# design.net
KiCad netlist of a schematic drawn in Altium Designer
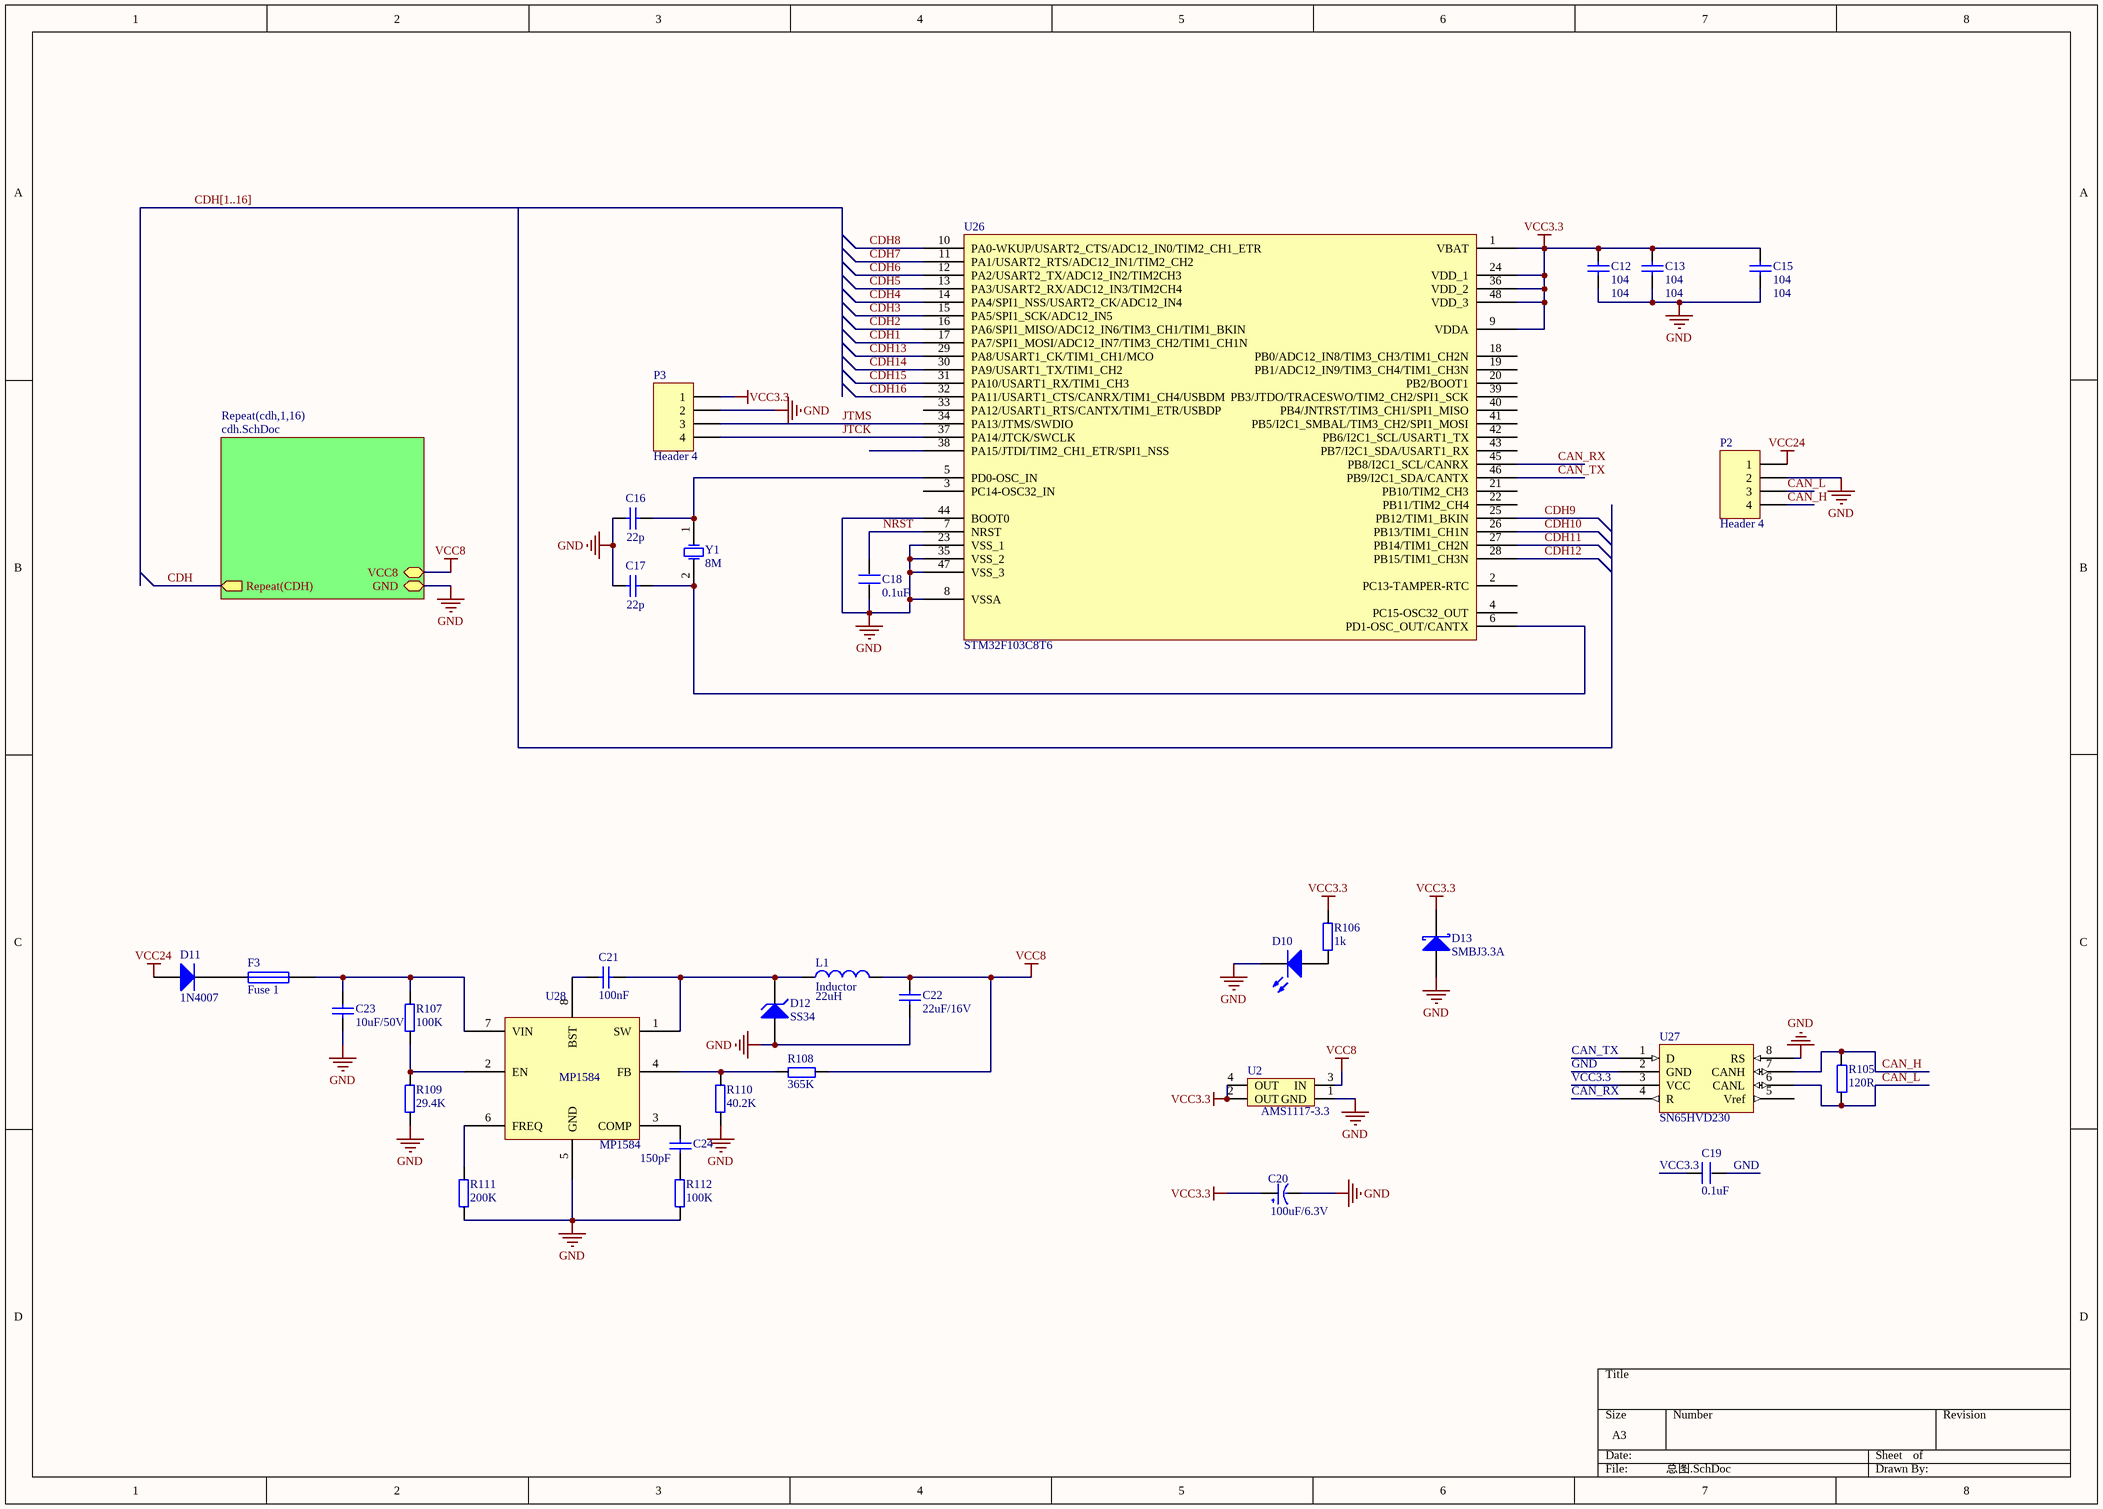
[diagram p0: 总图.SchDoc]

(export (version "E")
  (design (tool "Eeschema 10.0.6"))
  (components
    (comp (ref "C12")
      (value "104")
      (footprint "0603-CAP")
      (description "Capacitor")
      (fields (field (name "ALTIUM_VALUE") "104") (field (name "PUBLISHER") "Altium Limited"))
      (libsource (lib "Miscellaneous Devices") (part "Cap"))
    )
    (comp (ref "C13")
      (value "104")
      (footprint "0603-CAP")
      (description "Capacitor")
      (fields (field (name "ALTIUM_VALUE") "104") (field (name "PUBLISHER") "Altium Limited"))
      (libsource (lib "Miscellaneous Devices") (part "Cap"))
    )
    (comp (ref "C15")
      (value "104")
      (footprint "0603-CAP")
      (description "Capacitor")
      (fields (field (name "ALTIUM_VALUE") "104") (field (name "PUBLISHER") "Altium Limited"))
      (libsource (lib "Miscellaneous Devices") (part "Cap"))
    )
    (comp (ref "C16")
      (value "22p")
      (footprint "0603-CAP")
      (description "Capacitor")
      (fields (field (name "PUBLISHER") "Altium Limited"))
      (libsource (lib "Miscellaneous Devices") (part "Cap"))
    )
    (comp (ref "C17")
      (value "22p")
      (footprint "0603-CAP")
      (description "Capacitor")
      (fields (field (name "PUBLISHER") "Altium Limited"))
      (libsource (lib "Miscellaneous Devices") (part "Cap"))
    )
    (comp (ref "C18")
      (value "0.1uF")
      (footprint "0603-CAP")
      (libsource (lib "Explorer STM32F407封装库") (part "C"))
    )
    (comp (ref "C19")
      (value "0.1uF")
      (footprint "0603-CAP")
      (libsource (lib "Explorer STM32F407封装库") (part "C_3"))
    )
    (comp (ref "C20") (value "100uF/6.3V") (footprint "3216") (libsource (lib "WarShip V3_SCH") (part "CAP")))
    (comp (ref "C21")
      (value "100nF")
      (footprint "0603-CAP")
      (description "Capacitor (Semiconductor SIM Model)")
      (fields (field (name "Comment") "0.1uF") (field (name "PUBLISHER") "Altium Limited"))
      (libsource (lib "Miscellaneous Devices") (part "Cap Semi"))
    )
    (comp (ref "C22")
      (value "22uF/16V")
      (footprint "1206")
      (description "Capacitor (Semiconductor SIM Model)")
      (fields (field (name "PUBLISHER") "Altium Limited"))
      (libsource (lib "Miscellaneous Devices") (part "Cap Semi"))
    )
    (comp (ref "C23")
      (value "10uF/50V")
      (footprint "1206")
      (description "Capacitor (Semiconductor SIM Model)")
      (fields (field (name "PUBLISHER") "Altium Limited"))
      (libsource (lib "Miscellaneous Devices") (part "Cap Semi"))
    )
    (comp (ref "C24")
      (value "150pF")
      (footprint "0603-CAP")
      (description "Capacitor (Semiconductor SIM Model)")
      (fields (field (name "Comment") "0.1uF") (field (name "PUBLISHER") "Altium Limited"))
      (libsource (lib "Miscellaneous Devices") (part "Cap Semi"))
    )
    (comp (ref "D10")
      (value "LED0")
      (footprint "LC-0805_LED_S1")
      (description "Typical INFRARED GaAs LED")
      (fields (field (name "PUBLISHER") "Altium Limited"))
      (libsource (lib "继电器板_1") (part "LED0"))
    )
    (comp (ref "D11")
      (value "1N4007")
      (footprint "SMA(DO-214AC)_S1")
      (description "Default Diode")
      (fields (field (name "PUBLISHER") "Altium Limited"))
      (libsource (lib "Miscellaneous Devices") (part "Diode"))
    )
    (comp (ref "D12")
      (value "SS34")
      (footprint "SMA(DO-214AC)_S1")
      (description "Zener Diode")
      (fields (field (name "PUBLISHER") "Altium Limited"))
      (libsource (lib "Miscellaneous Devices") (part "D Zener"))
    )
    (comp (ref "D13")
      (value "SMBJ3.3A")
      (footprint "SMB(DO-214AA)_S1")
      (description "Schottky Rectifier")
      (fields (field (name "PUBLISHER") "Altium Limited"))
      (libsource (lib "Miscellaneous Devices") (part "Diode 18TQ045"))
    )
    (comp (ref "F3")
      (value "Fuse 1")
      (footprint "1206")
      (description "Fuse")
      (fields (field (name "PUBLISHER") "Altium Limited"))
      (libsource (lib "Miscellaneous Devices") (part "Fuse 1"))
    )
    (comp (ref "L1")
      (value "Inductor")
      (footprint "L-7*7*4mm-S")
      (fields (field (name "ALTIUM_VALUE") "22uH") (field (name "PUBLISHER") "Altium Limited"))
      (libsource (lib "Miscellaneous Devices") (part "Inductor"))
    )
    (comp (ref "P2")
      (value "Header 4")
      (footprint "DZ-4-3.5")
      (description "Header, 4-Pin")
      (fields (field (name "PUBLISHER") "Altium Limited"))
      (libsource (lib "Miscellaneous Connectors") (part "Header 4"))
    )
    (comp (ref "P3")
      (value "Header 4")
      (footprint "HDR1X4")
      (description "Header, 4-Pin")
      (fields (field (name "PUBLISHER") "Altium Limited"))
      (libsource (lib "Miscellaneous Connectors") (part "Header 4"))
    )
    (comp (ref "R105")
      (value "120R")
      (footprint "0603")
      (libsource (lib "Explorer STM32F407封装库") (part "R_2"))
    )
    (comp (ref "R106") (value "1k") (footprint "0603") (libsource (lib "Explorer STM32F407封装库") (part "R_2")))
    (comp (ref "R107")
      (value "100K")
      (footprint "0603")
      (libsource (lib "Explorer STM32F407封装库") (part "R_2"))
    )
    (comp (ref "R108")
      (value "365K")
      (footprint "0603")
      (libsource (lib "Explorer STM32F407封装库") (part "R_2"))
    )
    (comp (ref "R109")
      (value "29.4K")
      (footprint "0603")
      (libsource (lib "Explorer STM32F407封装库") (part "R_2"))
    )
    (comp (ref "R110")
      (value "40.2K")
      (footprint "0603")
      (libsource (lib "Explorer STM32F407封装库") (part "R_2"))
    )
    (comp (ref "R111")
      (value "200K")
      (footprint "0603")
      (libsource (lib "Explorer STM32F407封装库") (part "R_2"))
    )
    (comp (ref "R112")
      (value "100K")
      (footprint "0603")
      (libsource (lib "Explorer STM32F407封装库") (part "R_2"))
    )
    (comp (ref "U2")
      (value "AMS1117-3.3")
      (footprint "LC-SOT-223")
      (libsource (lib "WarShip V3_SCH") (part "AMS1117"))
    )
    (comp (ref "U26")
      (value "STM32F103C8T6")
      (footprint "LC-LQFP-48")
      (libsource (lib "Schlib1") (part "stm32f103v8t6"))
    )
    (comp (ref "U27")
      (value "SN65HVD230")
      (footprint "SOP-8")
      (libsource (lib "Explorer STM32F407封装库") (part "SN65HVD230D"))
    )
    (comp (ref "U28") (value "MP1584") (footprint "SO-8") (libsource (lib "磁导航") (part "MP1584EN")))
    (comp (ref "Y1")
      (value "8M")
      (footprint "XTAL_US1")
      (description "Crystal Oscillator")
      (fields (field (name "PUBLISHER") "Altium Limited"))
      (libsource (lib "Miscellaneous Devices") (part "XTAL"))
    )
  )
  (nets
    (net (code "1") (name "/CAN_H") (class "Default")
      (node (ref "P2") (pin "4") (pinfunction "4_4") (pintype "passive"))
      (node (ref "R105") (pin "2") (pintype "passive"))
      (node (ref "U27") (pin "7") (pinfunction "CANH_7") (pintype "bidirectional"))
    )
    (net (code "2") (name "/CAN_L") (class "Default")
      (node (ref "P2") (pin "3") (pinfunction "3_3") (pintype "passive"))
      (node (ref "R105") (pin "1") (pintype "passive"))
      (node (ref "U27") (pin "6") (pinfunction "CANL_6") (pintype "bidirectional"))
    )
    (net (code "3") (name "/CAN_RX") (class "Default")
      (node (ref "U26") (pin "45") (pinfunction "PB8/I2C1_SCL/CANRX_45") (pintype "passive"))
      (node (ref "U27") (pin "4") (pinfunction "R_4") (pintype "output"))
    )
    (net (code "4") (name "/CAN_TX") (class "Default")
      (node (ref "U26") (pin "46") (pinfunction "PB9/I2C1_SDA/CANTX_46") (pintype "passive"))
      (node (ref "U27") (pin "1") (pinfunction "D_1") (pintype "input"))
    )
    (net (code "6") (name "/CDH1") (class "Default")
      (node (ref "U26") (pin "17") (pinfunction "PA7/SPI1_MOSI/ADC12_IN7/TIM3_CH2/TIM1_CH1N_17") (pintype "passive"))
    )
    (net (code "7") (name "/CDH2") (class "Default")
      (node (ref "U26") (pin "16") (pinfunction "PA6/SPI1_MISO/ADC12_IN6/TIM3_CH1/TIM1_BKIN_16") (pintype "passive"))
    )
    (net (code "8") (name "/CDH3") (class "Default")
      (node (ref "U26") (pin "15") (pinfunction "PA5/SPI1_SCK/ADC12_IN5_15") (pintype "passive"))
    )
    (net (code "9") (name "/CDH4") (class "Default")
      (node (ref "U26") (pin "14") (pinfunction "PA4/SPI1_NSS/USART2_CK/ADC12_IN4_14") (pintype "passive"))
    )
    (net (code "10") (name "/CDH5") (class "Default")
      (node (ref "U26") (pin "13") (pinfunction "PA3/USART2_RX/ADC12_IN3/TIM2CH4_13") (pintype "passive"))
    )
    (net (code "11") (name "/CDH6") (class "Default")
      (node (ref "U26") (pin "12") (pinfunction "PA2/USART2_TX/ADC12_IN2/TIM2CH3_12") (pintype "passive"))
    )
    (net (code "12") (name "/CDH7") (class "Default")
      (node (ref "U26") (pin "11") (pinfunction "PA1/USART2_RTS/ADC12_IN1/TIM2_CH2_11") (pintype "passive"))
    )
    (net (code "13") (name "/CDH8") (class "Default")
      (node (ref "U26") (pin "10") (pinfunction "PA0-WKUP/USART2_CTS/ADC12_IN0/TIM2_CH1_ETR_10") (pintype "passive"))
    )
    (net (code "14") (name "/CDH9") (class "Default")
      (node (ref "U26") (pin "25") (pinfunction "PB12/TIM1_BKIN_25") (pintype "passive"))
    )
    (net (code "15") (name "/CDH10") (class "Default")
      (node (ref "U26") (pin "26") (pinfunction "PB13/TIM1_CH1N_26") (pintype "passive"))
    )
    (net (code "16") (name "/CDH11") (class "Default")
      (node (ref "U26") (pin "27") (pinfunction "PB14/TIM1_CH2N_27") (pintype "passive"))
    )
    (net (code "17") (name "/CDH12") (class "Default")
      (node (ref "U26") (pin "28") (pinfunction "PB15/TIM1_CH3N_28") (pintype "passive"))
    )
    (net (code "18") (name "/CDH13") (class "Default")
      (node (ref "U26") (pin "29") (pinfunction "PA8/USART1_CK/TIM1_CH1/MCO_29") (pintype "passive"))
    )
    (net (code "19") (name "/CDH14") (class "Default")
      (node (ref "U26") (pin "30") (pinfunction "PA9/USART1_TX/TIM1_CH2_30") (pintype "passive"))
    )
    (net (code "20") (name "/CDH15") (class "Default")
      (node (ref "U26") (pin "31") (pinfunction "PA10/USART1_RX/TIM1_CH3_31") (pintype "passive"))
    )
    (net (code "21") (name "/CDH16") (class "Default")
      (node (ref "U26") (pin "32") (pinfunction "PA11/USART1_CTS/CANRX/TIM1_CH4/USBDM_32") (pintype "passive"))
    )
    (net (code "23") (name "/JTCK") (class "Default")
      (node (ref "P3") (pin "4") (pinfunction "4_4") (pintype "passive"))
      (node (ref "U26") (pin "37") (pinfunction "PA14/JTCK/SWCLK_37") (pintype "passive"))
    )
    (net (code "24") (name "/JTMS") (class "Default")
      (node (ref "P3") (pin "3") (pinfunction "3_3") (pintype "passive"))
      (node (ref "U26") (pin "34") (pinfunction "PA13/JTMS/SWDIO_34") (pintype "passive"))
    )
    (net (code "25") (name "/NRST") (class "Default")
      (node (ref "C18") (pin "2") (pintype "passive"))
      (node (ref "U26") (pin "7") (pinfunction "NRST_7") (pintype "passive"))
    )
    (net (code "26") (name "GND") (class "Default")
      (node (ref "C12") (pin "2") (pinfunction "2_2") (pintype "passive"))
      (node (ref "C13") (pin "2") (pinfunction "2_2") (pintype "passive"))
      (node (ref "C15") (pin "2") (pinfunction "2_2") (pintype "passive"))
      (node (ref "C16") (pin "2") (pinfunction "2_2") (pintype "passive"))
      (node (ref "C17") (pin "2") (pinfunction "2_2") (pintype "passive"))
      (node (ref "C18") (pin "1") (pintype "passive"))
      (node (ref "C19") (pin "2") (pintype "passive"))
      (node (ref "C20") (pin "2") (pinfunction "GND_2") (pintype "passive"))
      (node (ref "C22") (pin "1") (pinfunction "1_1") (pintype "passive"))
      (node (ref "C23") (pin "2") (pinfunction "2_2") (pintype "passive"))
      (node (ref "D10") (pin "K") (pinfunction "K_K") (pintype "passive"))
      (node (ref "D12") (pin "1") (pinfunction "A_1") (pintype "passive"))
      (node (ref "D13") (pin "2") (pinfunction "A_2") (pintype "passive"))
      (node (ref "P2") (pin "2") (pinfunction "2_2") (pintype "passive"))
      (node (ref "P3") (pin "2") (pinfunction "2_2") (pintype "passive"))
      (node (ref "R109") (pin "2") (pintype "passive"))
      (node (ref "R110") (pin "2") (pintype "passive"))
      (node (ref "R111") (pin "2") (pintype "passive"))
      (node (ref "R112") (pin "2") (pintype "passive"))
      (node (ref "U2") (pin "1") (pinfunction "GND_1") (pintype "passive"))
      (node (ref "U26") (pin "23") (pinfunction "VSS_1_23") (pintype "passive"))
      (node (ref "U26") (pin "35") (pinfunction "VSS_2_35") (pintype "passive"))
      (node (ref "U26") (pin "44") (pinfunction "BOOT0_44") (pintype "passive"))
      (node (ref "U26") (pin "47") (pinfunction "VSS_3_47") (pintype "passive"))
      (node (ref "U26") (pin "8") (pinfunction "VSSA_8") (pintype "passive"))
      (node (ref "U27") (pin "2") (pinfunction "GND_2") (pintype "power_in"))
      (node (ref "U27") (pin "8") (pinfunction "RS_8") (pintype "input"))
      (node (ref "U28") (pin "5") (pinfunction "GND_5") (pintype "passive"))
    )
    (net (code "27") (name "Net-(C24-Pad1)") (class "Default")
      (node (ref "C24") (pin "1") (pinfunction "1_1") (pintype "passive"))
      (node (ref "R112") (pin "1") (pintype "passive"))
    )
    (net (code "28") (name "Net-(D10-PadA)") (class "Default")
      (node (ref "D10") (pin "A") (pinfunction "A_A") (pintype "passive"))
      (node (ref "R106") (pin "2") (pintype "passive"))
    )
    (net (code "29") (name "Net-(D11-K)") (class "Default")
      (node (ref "D11") (pin "2") (pinfunction "K_2") (pintype "passive"))
      (node (ref "F3") (pin "1") (pinfunction "1_1") (pintype "passive"))
    )
    (net (code "30") (name "Net-(D12-K)") (class "Default")
      (node (ref "C21") (pin "1") (pinfunction "1_1") (pintype "passive"))
      (node (ref "D12") (pin "2") (pinfunction "K_2") (pintype "passive"))
      (node (ref "L1") (pin "1") (pinfunction "1_1") (pintype "passive"))
      (node (ref "U28") (pin "1") (pinfunction "SW_1") (pintype "passive"))
    )
    (net (code "31") (name "Net-(U26-PD0-OSC_IN)") (class "Default")
      (node (ref "C16") (pin "1") (pinfunction "1_1") (pintype "passive"))
      (node (ref "U26") (pin "5") (pinfunction "PD0-OSC_IN_5") (pintype "passive"))
      (node (ref "Y1") (pin "1") (pinfunction "OSC1_1") (pintype "passive"))
    )
    (net (code "32") (name "Net-(U26-PD1-OSC_OUT{slash}CANTX)") (class "Default")
      (node (ref "C17") (pin "1") (pinfunction "1_1") (pintype "passive"))
      (node (ref "U26") (pin "6") (pinfunction "PD1-OSC_OUT/CANTX_6") (pintype "passive"))
      (node (ref "Y1") (pin "2") (pinfunction "OSC2_2") (pintype "passive"))
    )
    (net (code "33") (name "Net-(U28-BST)") (class "Default")
      (node (ref "C21") (pin "2") (pinfunction "2_2") (pintype "passive"))
      (node (ref "U28") (pin "8") (pinfunction "BST_8") (pintype "passive"))
    )
    (net (code "34") (name "Net-(U28-COMP)") (class "Default")
      (node (ref "C24") (pin "2") (pinfunction "2_2") (pintype "passive"))
      (node (ref "U28") (pin "3") (pinfunction "COMP_3") (pintype "passive"))
    )
    (net (code "35") (name "Net-(U28-EN)") (class "Default")
      (node (ref "R107") (pin "2") (pintype "passive"))
      (node (ref "R109") (pin "1") (pintype "passive"))
      (node (ref "U28") (pin "2") (pinfunction "EN_2") (pintype "passive"))
    )
    (net (code "36") (name "Net-(U28-FB)") (class "Default")
      (node (ref "R108") (pin "1") (pintype "passive"))
      (node (ref "R110") (pin "1") (pintype "passive"))
      (node (ref "U28") (pin "4") (pinfunction "FB_4") (pintype "passive"))
    )
    (net (code "37") (name "Net-(U28-FREQ)") (class "Default")
      (node (ref "R111") (pin "1") (pintype "passive"))
      (node (ref "U28") (pin "6") (pinfunction "FREQ_6") (pintype "passive"))
    )
    (net (code "38") (name "Net-(U28-VIN)") (class "Default")
      (node (ref "C23") (pin "1") (pinfunction "1_1") (pintype "passive"))
      (node (ref "F3") (pin "2") (pinfunction "2_2") (pintype "passive"))
      (node (ref "R107") (pin "1") (pintype "passive"))
      (node (ref "U28") (pin "7") (pinfunction "VIN_7") (pintype "passive"))
    )
    (net (code "39") (name "VCC3.3") (class "Default")
      (node (ref "C12") (pin "1") (pinfunction "1_1") (pintype "passive"))
      (node (ref "C13") (pin "1") (pinfunction "1_1") (pintype "passive"))
      (node (ref "C15") (pin "1") (pinfunction "1_1") (pintype "passive"))
      (node (ref "C19") (pin "1") (pintype "passive"))
      (node (ref "C20") (pin "1") (pinfunction "VCC_1") (pintype "passive"))
      (node (ref "D13") (pin "1") (pinfunction "K_1") (pintype "passive"))
      (node (ref "P3") (pin "1") (pinfunction "1_1") (pintype "passive"))
      (node (ref "R106") (pin "1") (pintype "passive"))
      (node (ref "U2") (pin "2") (pinfunction "OUT_2") (pintype "passive"))
      (node (ref "U2") (pin "4") (pinfunction "OUT_4") (pintype "passive"))
      (node (ref "U26") (pin "1") (pinfunction "VBAT_1") (pintype "passive"))
      (node (ref "U26") (pin "24") (pinfunction "VDD_1_24") (pintype "passive"))
      (node (ref "U26") (pin "36") (pinfunction "VDD_2_36") (pintype "passive"))
      (node (ref "U26") (pin "48") (pinfunction "VDD_3_48") (pintype "passive"))
      (node (ref "U26") (pin "9") (pinfunction "VDDA_9") (pintype "passive"))
      (node (ref "U27") (pin "3") (pinfunction "VCC_3") (pintype "power_in"))
    )
    (net (code "40") (name "VCC8") (class "Default")
      (node (ref "C22") (pin "2") (pinfunction "2_2") (pintype "passive"))
      (node (ref "L1") (pin "2") (pinfunction "2_2") (pintype "passive"))
      (node (ref "R108") (pin "2") (pintype "passive"))
      (node (ref "U2") (pin "3") (pinfunction "IN_3") (pintype "passive"))
    )
    (net (code "41") (name "VCC24") (class "Default")
      (node (ref "D11") (pin "1") (pinfunction "A_1") (pintype "passive"))
      (node (ref "P2") (pin "1") (pinfunction "1_1") (pintype "passive"))
    )
    (net (code "42") (name "unconnected-(U26-PA12{slash}USART1_RTS{slash}CANTX{slash}TIM1_ETR{slash}USBDP-Pad33)") (class "Default")
      (node (ref "U26") (pin "33") (pinfunction "PA12/USART1_RTS/CANTX/TIM1_ETR/USBDP_33") (pintype "passive"))
    )
    (net (code "43") (name "unconnected-(U26-PA15{slash}JTDI{slash}TIM2_CH1_ETR{slash}SPI1_NSS-Pad38)") (class "Default")
      (node (ref "U26") (pin "38") (pinfunction "PA15/JTDI/TIM2_CH1_ETR/SPI1_NSS_38") (pintype "passive"))
    )
    (net (code "44") (name "unconnected-(U26-PB0{slash}ADC12_IN8{slash}TIM3_CH3{slash}TIM1_CH2N-Pad18)") (class "Default")
      (node (ref "U26") (pin "18") (pinfunction "PB0/ADC12_IN8/TIM3_CH3/TIM1_CH2N_18") (pintype "passive"))
    )
    (net (code "45") (name "unconnected-(U26-PB1{slash}ADC12_IN9{slash}TIM3_CH4{slash}TIM1_CH3N-Pad19)") (class "Default")
      (node (ref "U26") (pin "19") (pinfunction "PB1/ADC12_IN9/TIM3_CH4/TIM1_CH3N_19") (pintype "passive"))
    )
    (net (code "46") (name "unconnected-(U26-PB2{slash}BOOT1-Pad20)") (class "Default")
      (node (ref "U26") (pin "20") (pinfunction "PB2/BOOT1_20") (pintype "passive"))
    )
    (net (code "47") (name "unconnected-(U26-PB3{slash}JTDO{slash}TRACESWO{slash}TIM2_CH2{slash}SPI1_SCK-Pad39)") (class "Default")
      (node (ref "U26") (pin "39") (pinfunction "PB3/JTDO/TRACESWO/TIM2_CH2/SPI1_SCK_39") (pintype "passive"))
    )
    (net (code "48") (name "unconnected-(U26-PB4{slash}JNTRST{slash}TIM3_CH1{slash}SPI1_MISO-Pad40)") (class "Default")
      (node (ref "U26") (pin "40") (pinfunction "PB4/JNTRST/TIM3_CH1/SPI1_MISO_40") (pintype "passive"))
    )
    (net (code "49") (name "unconnected-(U26-PB5{slash}I2C1_SMBAL{slash}TIM3_CH2{slash}SPI1_MOSI-Pad41)") (class "Default")
      (node (ref "U26") (pin "41") (pinfunction "PB5/I2C1_SMBAL/TIM3_CH2/SPI1_MOSI_41") (pintype "passive"))
    )
    (net (code "50") (name "unconnected-(U26-PB6{slash}I2C1_SCL{slash}USART1_TX-Pad42)") (class "Default")
      (node (ref "U26") (pin "42") (pinfunction "PB6/I2C1_SCL/USART1_TX_42") (pintype "passive"))
    )
    (net (code "51") (name "unconnected-(U26-PB7{slash}I2C1_SDA{slash}USART1_RX-Pad43)") (class "Default")
      (node (ref "U26") (pin "43") (pinfunction "PB7/I2C1_SDA/USART1_RX_43") (pintype "passive"))
    )
    (net (code "52") (name "unconnected-(U26-PB10{slash}TIM2_CH3-Pad21)") (class "Default")
      (node (ref "U26") (pin "21") (pinfunction "PB10/TIM2_CH3_21") (pintype "passive"))
    )
    (net (code "53") (name "unconnected-(U26-PB11{slash}TIM2_CH4-Pad22)") (class "Default")
      (node (ref "U26") (pin "22") (pinfunction "PB11/TIM2_CH4_22") (pintype "passive"))
    )
    (net (code "54") (name "unconnected-(U26-PC13-TAMPER-RTC-Pad2)") (class "Default")
      (node (ref "U26") (pin "2") (pinfunction "PC13-TAMPER-RTC_2") (pintype "passive"))
    )
    (net (code "55") (name "unconnected-(U26-PC14-OSC32_IN-Pad3)") (class "Default")
      (node (ref "U26") (pin "3") (pinfunction "PC14-OSC32_IN_3") (pintype "passive"))
    )
    (net (code "56") (name "unconnected-(U26-PC15-OSC32_OUT-Pad4)") (class "Default")
      (node (ref "U26") (pin "4") (pinfunction "PC15-OSC32_OUT_4") (pintype "passive"))
    )
    (net (code "57") (name "unconnected-(U27-Vref-Pad5)") (class "Default")
      (node (ref "U27") (pin "5") (pinfunction "Vref_5") (pintype "output"))
    )
  )
)
